# Digital__IO.net
KiCad netlist of a schematic drawn in Altium Designer
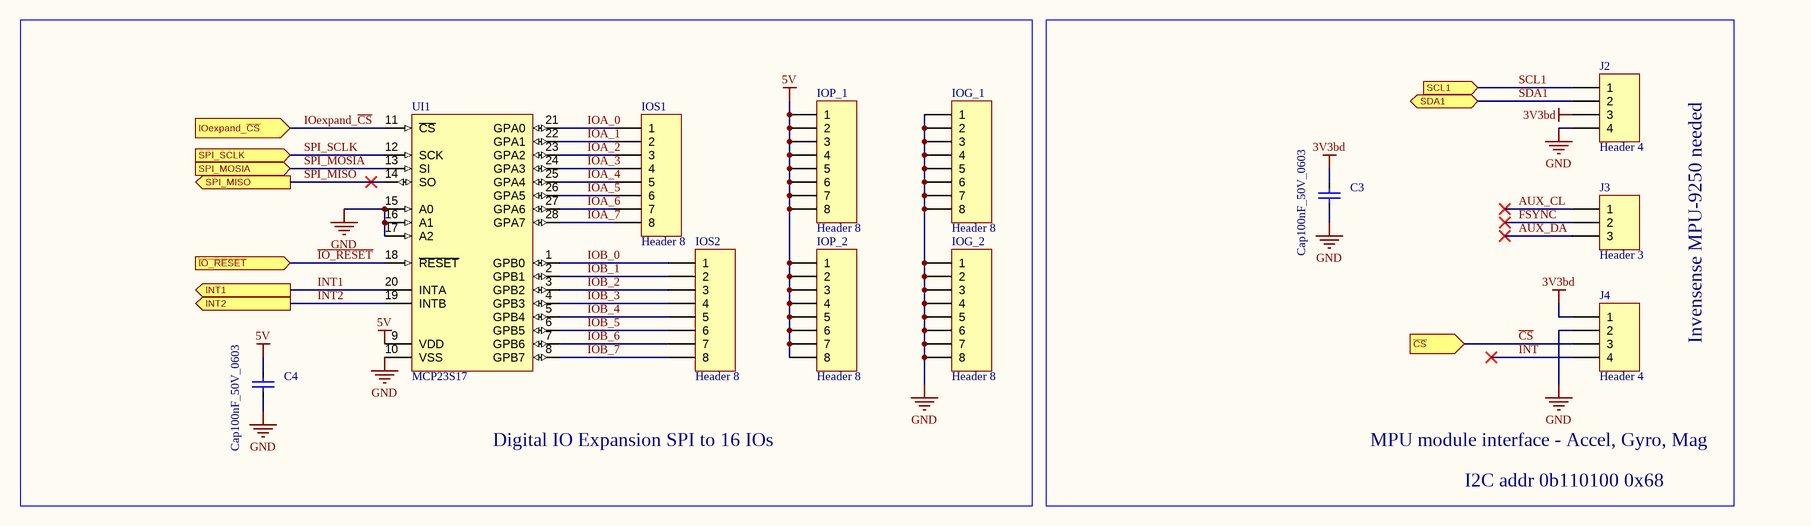
[diagram p0:  Digital_ IO.SchDoc]

(export (version "E")
  (design (tool "Eeschema 10.0.6"))
  (components
    (comp (ref "C3")
      (value "Cap100nF_50V_0603")
      (footprint "0603C_L")
      (libsource (lib "Advanced] Training Course - A365") (part "CAP General"))
    )
    (comp (ref "C4")
      (value "Cap100nF_50V_0603")
      (footprint "0603C_L")
      (libsource (lib "Advanced] Training Course - A365") (part "CAP General"))
    )
    (comp (ref "IOG_1")
      (value "Header 8")
      (footprint "HDR1X8")
      (description "Header, 8-Pin")
      (fields (field (name "PUBLISHER") "Altium Limited") (field (name "SOURCE") "WCT.SchLib"))
      (libsource (lib "Advanced] Training Course - A365") (part "Header 8"))
    )
    (comp (ref "IOG_2")
      (value "Header 8")
      (footprint "HDR1X8")
      (description "Header, 8-Pin")
      (fields (field (name "PUBLISHER") "Altium Limited") (field (name "SOURCE") "WCT.SchLib"))
      (libsource (lib "Advanced] Training Course - A365") (part "Header 8"))
    )
    (comp (ref "IOP_1")
      (value "Header 8")
      (footprint "HDR1X8")
      (description "Header, 8-Pin")
      (fields (field (name "PUBLISHER") "Altium Limited") (field (name "SOURCE") "WCT.SchLib"))
      (libsource (lib "Advanced] Training Course - A365") (part "Header 8"))
    )
    (comp (ref "IOP_2")
      (value "Header 8")
      (footprint "HDR1X8")
      (description "Header, 8-Pin")
      (fields (field (name "PUBLISHER") "Altium Limited") (field (name "SOURCE") "WCT.SchLib"))
      (libsource (lib "Advanced] Training Course - A365") (part "Header 8"))
    )
    (comp (ref "IOS1")
      (value "Header 8")
      (footprint "HDR1X8")
      (description "Header, 8-Pin")
      (fields (field (name "PUBLISHER") "Altium Limited") (field (name "SOURCE") "WCT.SchLib"))
      (libsource (lib "Advanced] Training Course - A365") (part "Header 8"))
    )
    (comp (ref "IOS2")
      (value "Header 8")
      (footprint "HDR1X8")
      (description "Header, 8-Pin")
      (fields (field (name "PUBLISHER") "Altium Limited") (field (name "SOURCE") "WCT.SchLib"))
      (libsource (lib "Advanced] Training Course - A365") (part "Header 8"))
    )
    (comp (ref "J2")
      (value "Header 4")
      (footprint "HDR1X4")
      (description "Header, 4-Pin")
      (fields (field (name "PUBLISHER") "Altium Limited") (field (name "SOURCE") "WCT.SchLib"))
      (libsource (lib "Advanced] Training Course - A365") (part "Header 4"))
    )
    (comp (ref "J3")
      (value "Header 3")
      (footprint "HDR1X3")
      (description "Header, 3-Pin")
      (fields (field (name "PUBLISHER") "Altium Limited") (field (name "SOURCE") "WCT.SchLib"))
      (libsource (lib "Advanced] Training Course - A365") (part "Header 3"))
    )
    (comp (ref "J4")
      (value "Header 4")
      (footprint "HDR1X4")
      (description "Header, 4-Pin")
      (fields (field (name "PUBLISHER") "Altium Limited") (field (name "SOURCE") "WCT.SchLib"))
      (libsource (lib "Advanced] Training Course - A365") (part "Header 4"))
    )
    (comp (ref "UI1")
      (value "MCP23S17")
      (footprint "SOIC-SO28_L")
      (description "16-Bit I/O Expander with Serial Interface, 28-Pin SOIC, Extended Temperature, Tape and Reel")
      (fields
        (field (name "MANUFACTURER") "Microchip")
        (field (name "MANUFACTURER PART NUMBER") "MCP23S17T-E/SO")
        (field (name "AVAILABLE PREVIEW IMAGES") "2D")
        (field (name "SOURCE") "WCT.SchLib")
      )
      (libsource (lib "Advanced] Training Course - A365") (part "MCP23S17"))
    )
  )
  (nets
    (net (code "1") (name "/AUX_CL") (class "Default")
      (node (ref "J3") (pin "1") (pinfunction "1_1") (pintype "passive+no_connect"))
    )
    (net (code "2") (name "/AUX_DA") (class "Default")
      (node (ref "J3") (pin "3") (pinfunction "3_3") (pintype "passive+no_connect"))
    )
    (net (code "3") (name "/FSYNC") (class "Default")
      (node (ref "J3") (pin "2") (pinfunction "2_2") (pintype "passive+no_connect"))
    )
    (net (code "4") (name "/INT") (class "Default")
      (node (ref "J4") (pin "4") (pinfunction "4_4") (pintype "passive+no_connect"))
    )
    (net (code "5") (name "/INT1") (class "Default")
      (node (ref "UI1") (pin "20") (pinfunction "INTA_20") (pintype "open_collector"))
    )
    (net (code "6") (name "/INT2") (class "Default")
      (node (ref "UI1") (pin "19") (pinfunction "INTB_19") (pintype "open_collector"))
    )
    (net (code "7") (name "/IOA_0") (class "Default")
      (node (ref "IOS1") (pin "1") (pinfunction "1_1") (pintype "passive"))
      (node (ref "UI1") (pin "21") (pinfunction "GPA0_21") (pintype "bidirectional"))
    )
    (net (code "8") (name "/IOA_1") (class "Default")
      (node (ref "IOS1") (pin "2") (pinfunction "2_2") (pintype "passive"))
      (node (ref "UI1") (pin "22") (pinfunction "GPA1_22") (pintype "bidirectional"))
    )
    (net (code "9") (name "/IOA_2") (class "Default")
      (node (ref "IOS1") (pin "3") (pinfunction "3_3") (pintype "passive"))
      (node (ref "UI1") (pin "23") (pinfunction "GPA2_23") (pintype "bidirectional"))
    )
    (net (code "10") (name "/IOA_3") (class "Default")
      (node (ref "IOS1") (pin "4") (pinfunction "4_4") (pintype "passive"))
      (node (ref "UI1") (pin "24") (pinfunction "GPA3_24") (pintype "bidirectional"))
    )
    (net (code "11") (name "/IOA_4") (class "Default")
      (node (ref "IOS1") (pin "5") (pinfunction "5_5") (pintype "passive"))
      (node (ref "UI1") (pin "25") (pinfunction "GPA4_25") (pintype "bidirectional"))
    )
    (net (code "12") (name "/IOA_5") (class "Default")
      (node (ref "IOS1") (pin "6") (pinfunction "6_6") (pintype "passive"))
      (node (ref "UI1") (pin "26") (pinfunction "GPA5_26") (pintype "bidirectional"))
    )
    (net (code "13") (name "/IOA_6") (class "Default")
      (node (ref "IOS1") (pin "7") (pinfunction "7_7") (pintype "passive"))
      (node (ref "UI1") (pin "27") (pinfunction "GPA6_27") (pintype "bidirectional"))
    )
    (net (code "14") (name "/IOA_7") (class "Default")
      (node (ref "IOS1") (pin "8") (pinfunction "8_8") (pintype "passive"))
      (node (ref "UI1") (pin "28") (pinfunction "GPA7_28") (pintype "bidirectional"))
    )
    (net (code "15") (name "/IOB_0") (class "Default")
      (node (ref "IOS2") (pin "1") (pinfunction "1_1") (pintype "passive"))
      (node (ref "UI1") (pin "1") (pinfunction "GPB0_1") (pintype "bidirectional"))
    )
    (net (code "16") (name "/IOB_1") (class "Default")
      (node (ref "IOS2") (pin "2") (pinfunction "2_2") (pintype "passive"))
      (node (ref "UI1") (pin "2") (pinfunction "GPB1_2") (pintype "bidirectional"))
    )
    (net (code "17") (name "/IOB_2") (class "Default")
      (node (ref "IOS2") (pin "3") (pinfunction "3_3") (pintype "passive"))
      (node (ref "UI1") (pin "3") (pinfunction "GPB2_3") (pintype "bidirectional"))
    )
    (net (code "18") (name "/IOB_3") (class "Default")
      (node (ref "IOS2") (pin "4") (pinfunction "4_4") (pintype "passive"))
      (node (ref "UI1") (pin "4") (pinfunction "GPB3_4") (pintype "bidirectional"))
    )
    (net (code "19") (name "/IOB_4") (class "Default")
      (node (ref "IOS2") (pin "5") (pinfunction "5_5") (pintype "passive"))
      (node (ref "UI1") (pin "5") (pinfunction "GPB4_5") (pintype "bidirectional"))
    )
    (net (code "20") (name "/IOB_5") (class "Default")
      (node (ref "IOS2") (pin "6") (pinfunction "6_6") (pintype "passive"))
      (node (ref "UI1") (pin "6") (pinfunction "GPB5_6") (pintype "bidirectional"))
    )
    (net (code "21") (name "/IOB_6") (class "Default")
      (node (ref "IOS2") (pin "7") (pinfunction "7_7") (pintype "passive"))
      (node (ref "UI1") (pin "7") (pinfunction "GPB6_7") (pintype "bidirectional"))
    )
    (net (code "22") (name "/IOB_7") (class "Default")
      (node (ref "IOS2") (pin "8") (pinfunction "8_8") (pintype "passive"))
      (node (ref "UI1") (pin "8") (pinfunction "GPB7_8") (pintype "bidirectional"))
    )
    (net (code "23") (name "/IO_RESET") (class "Default")
      (node (ref "UI1") (pin "18") (pinfunction "~{RESET}_18") (pintype "input"))
    )
    (net (code "24") (name "/IOexpand_~{CS}") (class "Default")
      (node (ref "UI1") (pin "11") (pinfunction "~{CS}_11") (pintype "input"))
    )
    (net (code "25") (name "/SCL1") (class "Default")
      (node (ref "J2") (pin "1") (pinfunction "1_1") (pintype "passive"))
    )
    (net (code "26") (name "/SDA1") (class "Default")
      (node (ref "J2") (pin "2") (pinfunction "2_2") (pintype "passive"))
    )
    (net (code "27") (name "/SPI_MISO") (class "Default")
      (node (ref "UI1") (pin "14") (pinfunction "SO_14") (pintype "bidirectional"))
    )
    (net (code "28") (name "/SPI_MOSIA") (class "Default")
      (node (ref "UI1") (pin "13") (pinfunction "SI_13") (pintype "input"))
    )
    (net (code "29") (name "/SPI_SCLK") (class "Default")
      (node (ref "UI1") (pin "12") (pinfunction "SCK_12") (pintype "input"))
    )
    (net (code "30") (name "/~{CS}") (class "Default")
      (node (ref "J4") (pin "3") (pinfunction "3_3") (pintype "passive"))
    )
    (net (code "31") (name "3V3bd") (class "Default")
      (node (ref "C3") (pin "2") (pinfunction "2_2") (pintype "passive"))
      (node (ref "J2") (pin "3") (pinfunction "3_3") (pintype "passive"))
      (node (ref "J4") (pin "1") (pinfunction "1_1") (pintype "passive"))
    )
    (net (code "32") (name "5V") (class "Default")
      (node (ref "C4") (pin "2") (pinfunction "2_2") (pintype "passive"))
      (node (ref "IOP_1") (pin "1") (pinfunction "1_1") (pintype "passive"))
      (node (ref "IOP_1") (pin "2") (pinfunction "2_2") (pintype "passive"))
      (node (ref "IOP_1") (pin "3") (pinfunction "3_3") (pintype "passive"))
      (node (ref "IOP_1") (pin "4") (pinfunction "4_4") (pintype "passive"))
      (node (ref "IOP_1") (pin "5") (pinfunction "5_5") (pintype "passive"))
      (node (ref "IOP_1") (pin "6") (pinfunction "6_6") (pintype "passive"))
      (node (ref "IOP_1") (pin "7") (pinfunction "7_7") (pintype "passive"))
      (node (ref "IOP_1") (pin "8") (pinfunction "8_8") (pintype "passive"))
      (node (ref "IOP_2") (pin "1") (pinfunction "1_1") (pintype "passive"))
      (node (ref "IOP_2") (pin "2") (pinfunction "2_2") (pintype "passive"))
      (node (ref "IOP_2") (pin "3") (pinfunction "3_3") (pintype "passive"))
      (node (ref "IOP_2") (pin "4") (pinfunction "4_4") (pintype "passive"))
      (node (ref "IOP_2") (pin "5") (pinfunction "5_5") (pintype "passive"))
      (node (ref "IOP_2") (pin "6") (pinfunction "6_6") (pintype "passive"))
      (node (ref "IOP_2") (pin "7") (pinfunction "7_7") (pintype "passive"))
      (node (ref "IOP_2") (pin "8") (pinfunction "8_8") (pintype "passive"))
      (node (ref "UI1") (pin "9") (pinfunction "VDD_9") (pintype "power_in"))
    )
    (net (code "33") (name "GND") (class "Default")
      (node (ref "C3") (pin "1") (pinfunction "1_1") (pintype "passive"))
      (node (ref "C4") (pin "1") (pinfunction "1_1") (pintype "passive"))
      (node (ref "IOG_1") (pin "1") (pinfunction "1_1") (pintype "passive"))
      (node (ref "IOG_1") (pin "2") (pinfunction "2_2") (pintype "passive"))
      (node (ref "IOG_1") (pin "3") (pinfunction "3_3") (pintype "passive"))
      (node (ref "IOG_1") (pin "4") (pinfunction "4_4") (pintype "passive"))
      (node (ref "IOG_1") (pin "5") (pinfunction "5_5") (pintype "passive"))
      (node (ref "IOG_1") (pin "6") (pinfunction "6_6") (pintype "passive"))
      (node (ref "IOG_1") (pin "7") (pinfunction "7_7") (pintype "passive"))
      (node (ref "IOG_1") (pin "8") (pinfunction "8_8") (pintype "passive"))
      (node (ref "IOG_2") (pin "1") (pinfunction "1_1") (pintype "passive"))
      (node (ref "IOG_2") (pin "2") (pinfunction "2_2") (pintype "passive"))
      (node (ref "IOG_2") (pin "3") (pinfunction "3_3") (pintype "passive"))
      (node (ref "IOG_2") (pin "4") (pinfunction "4_4") (pintype "passive"))
      (node (ref "IOG_2") (pin "5") (pinfunction "5_5") (pintype "passive"))
      (node (ref "IOG_2") (pin "6") (pinfunction "6_6") (pintype "passive"))
      (node (ref "IOG_2") (pin "7") (pinfunction "7_7") (pintype "passive"))
      (node (ref "IOG_2") (pin "8") (pinfunction "8_8") (pintype "passive"))
      (node (ref "J2") (pin "4") (pinfunction "4_4") (pintype "passive"))
      (node (ref "J4") (pin "2") (pinfunction "2_2") (pintype "passive"))
      (node (ref "UI1") (pin "10") (pinfunction "VSS_10") (pintype "power_in"))
      (node (ref "UI1") (pin "15") (pinfunction "A0_15") (pintype "input"))
      (node (ref "UI1") (pin "16") (pinfunction "A1_16") (pintype "input"))
      (node (ref "UI1") (pin "17") (pinfunction "A2_17") (pintype "input"))
    )
  )
)
